# Converter_Current_to_Voltage.net
KiCad netlist of a schematic drawn in Altium Designer
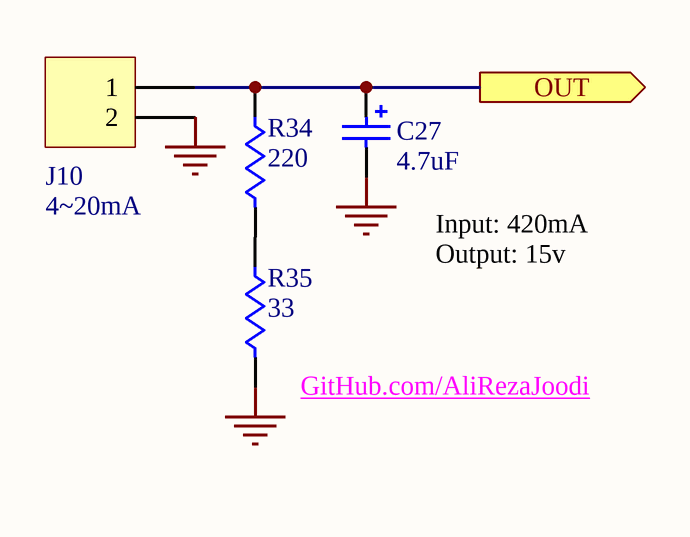
[diagram p0: Converter_Current to Voltage.SchDoc]

(export (version "E")
  (design (tool "Eeschema 10.0.6"))
  (components
    (comp (ref "C27")
      (value "4.7uF")
      (footprint "CAPPR2.5-6.3x5")
      (description "Polarized Capacitor (Radial)")
      (fields
        (field (name "MANUFACTURER") "Generic Components")
        (field (name "Comment") "Cap Pol1")
        (field (name "PUBLISHER") "Altium Limited")
      )
      (libsource (lib "Miscellaneous Devices") (part "Cap Pol1"))
    )
    (comp (ref "J10")
      (value "Header 2")
      (footprint "Fonics_2PIN_1")
      (description "Header, 2-Pin")
      (fields (field (name "PUBLISHER") "Altium Limited"))
      (libsource (lib "Miscellaneous Connectors") (part "Header 2"))
    )
    (comp (ref "R34")
      (value "220")
      (footprint "AXIAL-0.4")
      (description "Resistor")
      (fields
        (field (name "MANUFACTURER") "Generic Components")
        (field (name "Comment") "Res1")
        (field (name "PUBLISHER") "Altium Limited")
      )
      (libsource (lib "Miscellaneous Devices") (part "Res1"))
    )
    (comp (ref "R35")
      (value "33")
      (footprint "AXIAL-0.4")
      (description "Resistor")
      (fields
        (field (name "MANUFACTURER") "Generic Components")
        (field (name "Comment") "Res1")
        (field (name "PUBLISHER") "Altium Limited")
      )
      (libsource (lib "Miscellaneous Devices") (part "Res1"))
    )
  )
  (nets
    (net (code "1") (name "/OUT") (class "Default")
      (node (ref "C27") (pin "1") (pinfunction "1_1") (pintype "passive"))
      (node (ref "J10") (pin "1") (pinfunction "1_1") (pintype "passive"))
      (node (ref "R34") (pin "1") (pinfunction "1_1") (pintype "passive"))
    )
    (net (code "2") (name "GND") (class "Default")
      (node (ref "C27") (pin "2") (pinfunction "2_2") (pintype "passive"))
      (node (ref "J10") (pin "2") (pinfunction "2_2") (pintype "passive"))
      (node (ref "R35") (pin "2") (pinfunction "2_2") (pintype "passive"))
    )
    (net (code "3") (name "Net-(R34-Pad2)") (class "Default")
      (node (ref "R34") (pin "2") (pinfunction "2_2") (pintype "passive"))
      (node (ref "R35") (pin "1") (pinfunction "1_1") (pintype "passive"))
    )
  )
)
